# Top.net
KiCad netlist of a schematic drawn in Altium Designer
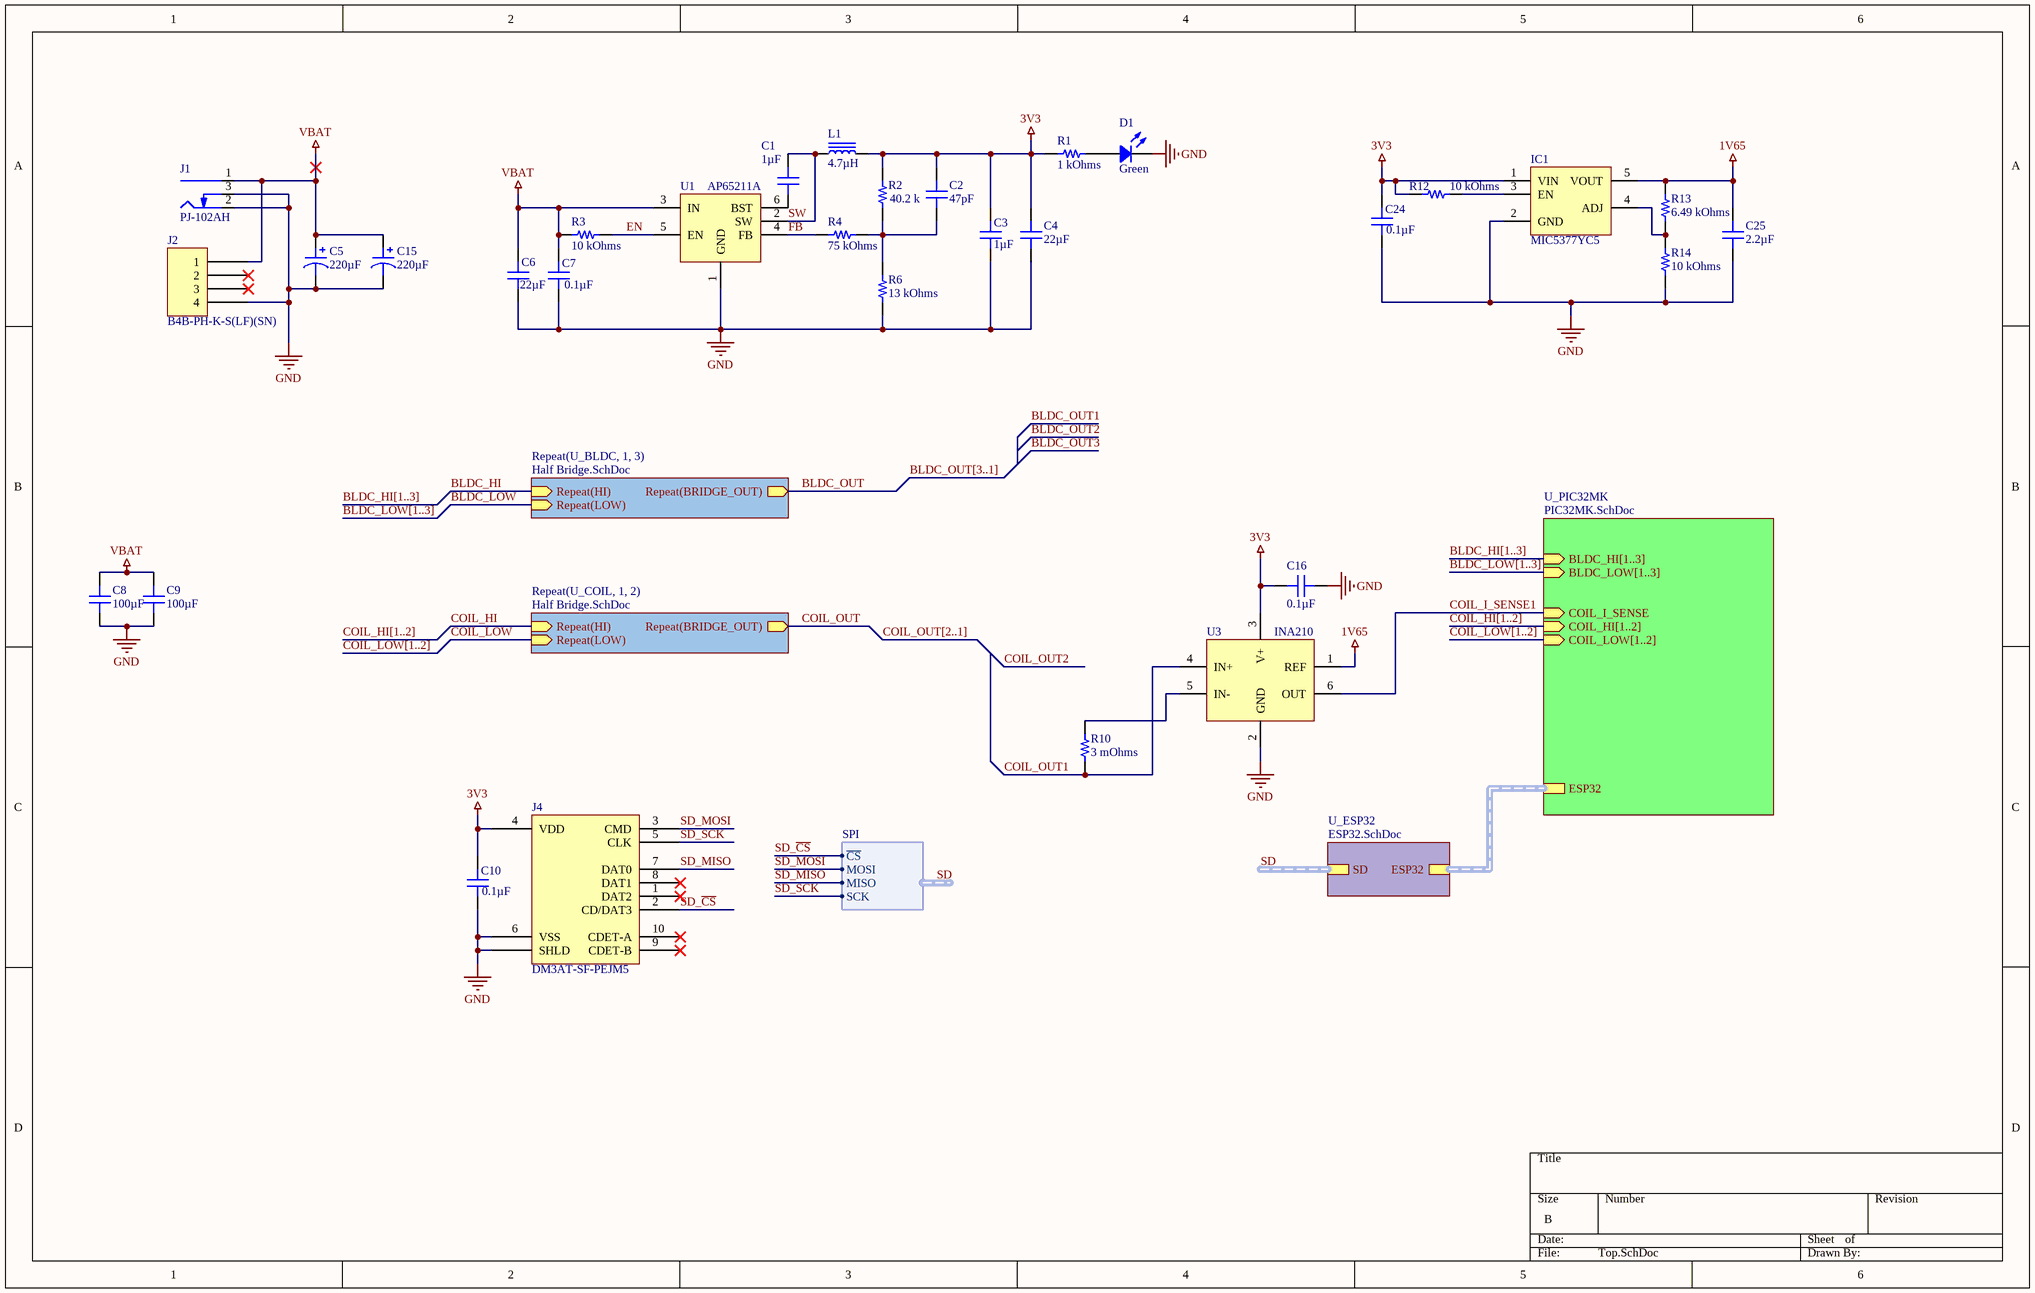
[diagram p0: Top.SchDoc]

(export (version "E")
  (design (tool "Eeschema 10.0.6"))
  (components
    (comp (ref "C1")
      (value "1µF")
      (footprint "CAP 0603_1608")
      (description "CAP CER 1UF 25V X7R 0603")
      (fields
        (field (name "PART NUMBER") "GCJ188R71E105KA01D")
        (field (name "MANUFACTURER") "Murata Electronics")
      )
      (libsource (lib "Celestial Altium Library - altium_library") (part "Capacitor"))
    )
    (comp (ref "C2")
      (value "47pF")
      (footprint "CAP 0603_1608")
      (description "CAP CER 47PF 100V NP0 0603")
      (fields
        (field (name "PART NUMBER") "C1608NP02A470J080AA")
        (field (name "MANUFACTURER") "TDK Corporation")
      )
      (libsource (lib "Celestial Altium Library - altium_library") (part "Capacitor"))
    )
    (comp (ref "C3")
      (value "1µF")
      (footprint "CAP 0603_1608")
      (description "CAP CER 1UF 25V X7R 0603")
      (fields
        (field (name "PART NUMBER") "GCJ188R71E105KA01D")
        (field (name "MANUFACTURER") "Murata Electronics")
      )
      (libsource (lib "Celestial Altium Library - altium_library") (part "Capacitor"))
    )
    (comp (ref "C4")
      (value "22µF")
      (footprint "CAP 0805_2012")
      (description "CAP CER 22UF 16V X5R 0805")
      (fields
        (field (name "PART NUMBER") "CL21A226MOQNNNE")
        (field (name "MANUFACTURER") "Samsung Electro-Mechanics")
      )
      (libsource (lib "Celestial Altium Library - altium_library") (part "Capacitor"))
    )
    (comp (ref "C5")
      (value "220µF")
      (footprint "CAP POL 2917_7343")
      (description "CAP TANT 220UF 10% 16V 2917")
      (fields (field (name "PART NUMBER") "T510X227K016ATE040") (field (name "MANUFACTURER") "KEMET"))
      (libsource (lib "Celestial Altium Library - altium_library") (part "Polarised Capacitor"))
    )
    (comp (ref "C6")
      (value "22µF")
      (footprint "CAP 0805_2012")
      (description "CAP CER 10UF 25V X7S 0805")
      (fields
        (field (name "PART NUMBER") "C2012X7S1E106K125AC")
        (field (name "MANUFACTURER") "TDK Corporation")
      )
      (libsource (lib "Celestial Altium Library - altium_library") (part "Capacitor"))
    )
    (comp (ref "C7")
      (value "0.1µF")
      (footprint "CAP 0603_1608")
      (description "CAP CER 0.1UF 100V 0603 EPOXY")
      (fields
        (field (name "PART NUMBER") "GCG188R92A104KA03D")
        (field (name "MANUFACTURER") "Murata Electronics")
      )
      (libsource (lib "Celestial Altium Library - altium_library") (part "Capacitor"))
    )
    (comp (ref "C8")
      (value "100µF")
      (footprint "CAP 1210_3225 - 2.8MM")
      (description "CAP CER 100UF 16V X5R 1210")
      (fields (field (name "PART NUMBER") "EMK325ABJ107MM-P") (field (name "MANUFACTURER") "Taiyo Yuden"))
      (libsource (lib "Celestial Altium Library - altium_library") (part "Capacitor"))
    )
    (comp (ref "C9")
      (value "100µF")
      (footprint "CAP 1210_3225 - 2.8MM")
      (description "CAP CER 100UF 16V X5R 1210")
      (fields (field (name "PART NUMBER") "EMK325ABJ107MM-P") (field (name "MANUFACTURER") "Taiyo Yuden"))
      (libsource (lib "Celestial Altium Library - altium_library") (part "Capacitor"))
    )
    (comp (ref "C10")
      (value "0.1µF")
      (footprint "CAP 0603_1608")
      (description "CAP CER 0.1UF 100V 0603 EPOXY")
      (fields
        (field (name "PART NUMBER") "GCG188R92A104KA03D")
        (field (name "MANUFACTURER") "Murata Electronics")
      )
      (libsource (lib "Celestial Altium Library - altium_library") (part "Capacitor"))
    )
    (comp (ref "C15")
      (value "220µF")
      (footprint "CAP POL 2917_7343")
      (description "CAP TANT 220UF 10% 16V 2917")
      (fields (field (name "PART NUMBER") "T510X227K016ATE040") (field (name "MANUFACTURER") "KEMET"))
      (libsource (lib "Celestial Altium Library - altium_library") (part "Polarised Capacitor"))
    )
    (comp (ref "C16")
      (value "0.1µF")
      (footprint "CAP 0603_1608")
      (description "CAP CER 0.1UF 100V 0603 EPOXY")
      (fields
        (field (name "PART NUMBER") "GCG188R92A104KA03D")
        (field (name "MANUFACTURER") "Murata Electronics")
      )
      (libsource (lib "Celestial Altium Library - altium_library") (part "Capacitor"))
    )
    (comp (ref "C24")
      (value "0.1µF")
      (footprint "CAP 0603_1608")
      (description "CAP CER 0.1UF 100V 0603 EPOXY")
      (fields
        (field (name "PART NUMBER") "GCG188R92A104KA03D")
        (field (name "MANUFACTURER") "Murata Electronics")
      )
      (libsource (lib "Celestial Altium Library - altium_library") (part "Capacitor"))
    )
    (comp (ref "C25")
      (value "2.2µF")
      (footprint "CAP 0603_1608")
      (description "CAP CER 2.2UF 6.3V Y5V 0603")
      (fields (field (name "PART NUMBER") "CC0603ZRY5V5BB225") (field (name "MANUFACTURER") "Yageo"))
      (libsource (lib "Celestial Altium Library - altium_library") (part "Capacitor"))
    )
    (comp (ref "D1")
      (value "Green")
      (footprint "LED 0603_1608 GREEN")
      (description "1.6X0.8MM LC GREEN PIXSOLED DOME")
      (fields (field (name "PART NUMBER") "XZCDGK53W-8VF") (field (name "MANUFACTURER") "SunLED"))
      (libsource (lib "Celestial Altium Library - altium_library") (part "LED"))
    )
    (comp (ref "IC1")
      (value "MIC5377YC5")
      (footprint "TI SOT-23-5 DBV")
      (description "IC REG LIN POS ADJ 150MA SOT23-5")
      (fields (field (name "MANUFACTURER") "Texas Instruments"))
      (libsource (lib "IC") (part "MIC5377YC5"))
    )
    (comp (ref "J1")
      (value "PJ-102AH")
      (footprint "CUI PJ-102AH")
      (description "CONN PWR JACK 2X5.5MM SOLDER")
      (fields (field (name "MANUFACTURER") "CUI Devices"))
      (libsource (lib "Celestial Altium Library - altium_library") (part "Barrel Connector"))
    )
    (comp (ref "J2")
      (value "B4B-PH-K-S(LF)(SN)")
      (footprint "JST B4B-PH-K")
      (description "CONN HEADER VERT 4POS 2MM")
      (fields (field (name "MANUFACTURER") "JST Sales America Inc."))
      (libsource (lib "Celestial Altium Library - altium_library") (part "4 Pin"))
    )
    (comp (ref "J4")
      (value "DM3AT-SF-PEJM5")
      (footprint "HIROSE DM3AT-SF-PEJM5")
      (description "CONN MICRO SD CARD PUSH-PUSH R/A")
      (fields (field (name "MANUFACTURER") "Hirose Electric Co Ltd"))
      (libsource (lib "Celestial Altium Library - altium_library") (part "Hirose DM3 MicroSD"))
    )
    (comp (ref "L1")
      (value "4.7µH")
      (footprint "IND 1008_2520")
      (description "FIXED IND 4.7UH 1A 110 MOHM SMD")
      (fields (field (name "PART NUMBER") "MLP2520S4R7ST0S1") (field (name "MANUFACTURER") "TDK Corporation"))
      (libsource (lib "Celestial Altium Library - altium_library") (part "Inductor"))
    )
    (comp (ref "R1")
      (value "1 kOhms")
      (footprint "RES 0603_1608")
      (description "RES 1K OHM 0.5% 1/10W 0603")
      (fields
        (field (name "PART NUMBER") "RNCF0603DTE1K00")
        (field (name "MANUFACTURER") "Stackpole Electronics Inc")
      )
      (libsource (lib "Celestial Altium Library - altium_library") (part "Resistor"))
    )
    (comp (ref "R2")
      (value "40.2 k")
      (footprint "RES 0603_1608")
      (description "RES SMD 40.2KOHM 0.5% 1/10W 0603")
      (fields (field (name "PART NUMBER") "RT0603DRD0740K2L") (field (name "MANUFACTURER") "Yageo"))
      (libsource (lib "Celestial Altium Library - altium_library") (part "Resistor"))
    )
    (comp (ref "R3")
      (value "10 kOhms")
      (footprint "RES 0603_1608")
      (description "RES 10K OHM 0.1% 1/16W 0603")
      (fields
        (field (name "PART NUMBER") "RNCS0603BKE10K0")
        (field (name "MANUFACTURER") "Stackpole Electronics Inc")
      )
      (libsource (lib "Celestial Altium Library - altium_library") (part "Resistor"))
    )
    (comp (ref "R4")
      (value "75 kOhms")
      (footprint "RES 0603_1608")
      (description "RES SMD 75K OHM 5% 1/10W 0603")
      (fields (field (name "PART NUMBER") "CR0603-JW-753ELF") (field (name "MANUFACTURER") "Bourns Inc."))
      (libsource (lib "Celestial Altium Library - altium_library") (part "Resistor"))
    )
    (comp (ref "R6")
      (value "13 kOhms")
      (footprint "RES 0603_1608")
      (description "RES SMD 13K OHM 0.1% 1/10W 0603")
      (fields (field (name "PART NUMBER") "RG1608P-133-B-T5") (field (name "MANUFACTURER") "Susumu"))
      (libsource (lib "Celestial Altium Library - altium_library") (part "Resistor"))
    )
    (comp (ref "R10")
      (value "3 mOhms")
      (footprint "STACKPOLE CSR0805")
      (description "RES 0.003 OHM 2% 1/3W 0603")
      (fields (field (name "PART NUMBER") "LVT06R0030GER") (field (name "MANUFACTURER") "Ohmite"))
      (libsource (lib "Celestial Altium Library - altium_library") (part "Resistor"))
    )
    (comp (ref "R12")
      (value "10 kOhms")
      (footprint "RES 0603_1608")
      (description "RES 10K OHM 0.1% 1/16W 0603")
      (fields
        (field (name "PART NUMBER") "RNCS0603BKE10K0")
        (field (name "MANUFACTURER") "Stackpole Electronics Inc")
      )
      (libsource (lib "Celestial Altium Library - altium_library") (part "Resistor"))
    )
    (comp (ref "R13")
      (value "6.49 kOhms")
      (footprint "RES 0603_1608")
      (description "RES SMD 6.49K OHM 1% 1/10W 0603")
      (fields (field (name "PART NUMBER") "RC0603FR-076K49L") (field (name "MANUFACTURER") "Yageo"))
      (libsource (lib "Celestial Altium Library - altium_library") (part "Resistor"))
    )
    (comp (ref "R14")
      (value "10 kOhms")
      (footprint "RES 0603_1608")
      (description "RES 10K OHM 0.1% 1/16W 0603")
      (fields
        (field (name "PART NUMBER") "RNCS0603BKE10K0")
        (field (name "MANUFACTURER") "Stackpole Electronics Inc")
      )
      (libsource (lib "Celestial Altium Library - altium_library") (part "Resistor"))
    )
    (comp (ref "U1")
      (value "AP65211A")
      (footprint "TSOT-26-6")
      (description "ADJ step down Buck")
      (libsource (lib "IC") (part "AP65211A"))
    )
    (comp (ref "U3")
      (value "INA210")
      (footprint "TI SC70-6 DCK")
      (description "Current sense amplifier")
      (libsource (lib "IC") (part "INA210"))
    )
  )
  (nets
    (net (code "24") (name "/COIL_I_SENSE1") (class "Default")
      (node (ref "U3") (pin "6") (pinfunction "OUT_6") (pintype "passive"))
    )
    (net (code "28") (name "/COIL_OUT1") (class "Default")
      (node (ref "R10") (pin "1") (pinfunction "1_1") (pintype "passive"))
      (node (ref "U3") (pin "4") (pinfunction "IN+_4") (pintype "passive"))
    )
    (net (code "31") (name "/EN") (class "Default")
      (node (ref "R3") (pin "1") (pinfunction "1_1") (pintype "passive"))
      (node (ref "U1") (pin "5") (pinfunction "EN_5") (pintype "passive"))
    )
    (net (code "33") (name "/FB") (class "Default")
      (node (ref "R4") (pin "1") (pinfunction "1_1") (pintype "passive"))
      (node (ref "U1") (pin "4") (pinfunction "FB_4") (pintype "passive"))
    )
    (net (code "34") (name "/SD_MISO") (class "Default")
      (node (ref "J4") (pin "7") (pinfunction "DAT0_7") (pintype "passive"))
    )
    (net (code "35") (name "/SD_MOSI") (class "Default")
      (node (ref "J4") (pin "3") (pinfunction "CMD_3") (pintype "passive"))
    )
    (net (code "36") (name "/SD_SCK") (class "Default")
      (node (ref "J4") (pin "5") (pinfunction "CLK_5") (pintype "passive"))
    )
    (net (code "37") (name "/SD_~{CS}") (class "Default")
      (node (ref "J4") (pin "2") (pinfunction "CD/DAT3_2") (pintype "passive"))
    )
    (net (code "39") (name "/SW") (class "Default")
      (node (ref "C1") (pin "1") (pinfunction "1_1") (pintype "passive"))
      (node (ref "L1") (pin "1") (pinfunction "1_1") (pintype "passive"))
      (node (ref "U1") (pin "2") (pinfunction "SW_2") (pintype "passive"))
    )
    (net (code "41") (name "1V65") (class "Default")
      (node (ref "C25") (pin "2") (pinfunction "2_2") (pintype "passive"))
      (node (ref "IC1") (pin "5") (pinfunction "VOUT_5") (pintype "passive"))
      (node (ref "R13") (pin "2") (pinfunction "2_2") (pintype "passive"))
      (node (ref "U3") (pin "1") (pinfunction "REF_1") (pintype "passive"))
    )
    (net (code "42") (name "3V3") (class "Default")
      (node (ref "C10") (pin "1") (pinfunction "1_1") (pintype "passive"))
      (node (ref "C16") (pin "1") (pinfunction "1_1") (pintype "passive"))
      (node (ref "C2") (pin "2") (pinfunction "2_2") (pintype "passive"))
      (node (ref "C24") (pin "1") (pinfunction "1_1") (pintype "passive"))
      (node (ref "C3") (pin "2") (pinfunction "2_2") (pintype "passive"))
      (node (ref "C4") (pin "2") (pinfunction "2_2") (pintype "passive"))
      (node (ref "IC1") (pin "1") (pinfunction "VIN_1") (pintype "passive"))
      (node (ref "J4") (pin "4") (pinfunction "VDD_4") (pintype "passive"))
      (node (ref "L1") (pin "2") (pinfunction "2_2") (pintype "passive"))
      (node (ref "R1") (pin "1") (pinfunction "1_1") (pintype "passive"))
      (node (ref "R12") (pin "2") (pinfunction "2_2") (pintype "passive"))
      (node (ref "R2") (pin "2") (pinfunction "2_2") (pintype "passive"))
      (node (ref "U3") (pin "3") (pinfunction "V+_3") (pintype "passive"))
    )
    (net (code "43") (name "GND") (class "Default")
      (node (ref "C10") (pin "2") (pinfunction "2_2") (pintype "passive"))
      (node (ref "C15") (pin "2") (pinfunction "2_2") (pintype "passive"))
      (node (ref "C16") (pin "2") (pinfunction "2_2") (pintype "passive"))
      (node (ref "C24") (pin "2") (pinfunction "2_2") (pintype "passive"))
      (node (ref "C25") (pin "1") (pinfunction "1_1") (pintype "passive"))
      (node (ref "C3") (pin "1") (pinfunction "1_1") (pintype "passive"))
      (node (ref "C4") (pin "1") (pinfunction "1_1") (pintype "passive"))
      (node (ref "C5") (pin "2") (pinfunction "2_2") (pintype "passive"))
      (node (ref "C6") (pin "1") (pinfunction "1_1") (pintype "passive"))
      (node (ref "C7") (pin "2") (pinfunction "2_2") (pintype "passive"))
      (node (ref "C8") (pin "1") (pinfunction "1_1") (pintype "passive"))
      (node (ref "C9") (pin "1") (pinfunction "1_1") (pintype "passive"))
      (node (ref "D1") (pin "2") (pinfunction "2_2") (pintype "passive"))
      (node (ref "IC1") (pin "2") (pinfunction "GND_2") (pintype "passive"))
      (node (ref "J1") (pin "2") (pinfunction "Outer_2") (pintype "passive"))
      (node (ref "J1") (pin "3") (pinfunction "SW_3") (pintype "passive"))
      (node (ref "J2") (pin "4") (pinfunction "4_4") (pintype "passive"))
      (node (ref "J4") (pin "6") (pinfunction "VSS_6") (pintype "passive"))
      (node (ref "J4") (pin "S") (pinfunction "SHLD_S") (pintype "passive"))
      (node (ref "R14") (pin "1") (pinfunction "1_1") (pintype "passive"))
      (node (ref "R6") (pin "1") (pinfunction "1_1") (pintype "passive"))
      (node (ref "U1") (pin "1") (pinfunction "GND_1") (pintype "passive"))
      (node (ref "U3") (pin "2") (pinfunction "GND_2") (pintype "passive"))
    )
    (net (code "44") (name "Net-(C2-Pad1)") (class "Default")
      (node (ref "C2") (pin "1") (pinfunction "1_1") (pintype "passive"))
      (node (ref "R2") (pin "1") (pinfunction "1_1") (pintype "passive"))
      (node (ref "R4") (pin "2") (pinfunction "2_2") (pintype "passive"))
      (node (ref "R6") (pin "2") (pinfunction "2_2") (pintype "passive"))
    )
    (net (code "45") (name "Net-(D1-Pad1)") (class "Default")
      (node (ref "D1") (pin "1") (pinfunction "1_1") (pintype "passive"))
      (node (ref "R1") (pin "2") (pinfunction "2_2") (pintype "passive"))
    )
    (net (code "46") (name "Net-(IC1-ADJ)") (class "Default")
      (node (ref "IC1") (pin "4") (pinfunction "ADJ_4") (pintype "passive"))
      (node (ref "R13") (pin "1") (pinfunction "1_1") (pintype "passive"))
      (node (ref "R14") (pin "2") (pinfunction "2_2") (pintype "passive"))
    )
    (net (code "47") (name "Net-(IC1-EN)") (class "Default")
      (node (ref "IC1") (pin "3") (pinfunction "EN_3") (pintype "passive"))
      (node (ref "R12") (pin "1") (pinfunction "1_1") (pintype "passive"))
    )
    (net (code "48") (name "Net-(U1-BST)") (class "Default")
      (node (ref "C1") (pin "2") (pinfunction "2_2") (pintype "passive"))
      (node (ref "U1") (pin "6") (pinfunction "BST_6") (pintype "passive"))
    )
    (net (code "49") (name "Net-(U3-IN-)") (class "Default")
      (node (ref "R10") (pin "2") (pinfunction "2_2") (pintype "passive"))
      (node (ref "U3") (pin "5") (pinfunction "IN-_5") (pintype "passive"))
    )
    (net (code "50") (name "VBAT") (class "Default")
      (node (ref "C15") (pin "1") (pinfunction "1_1") (pintype "passive"))
      (node (ref "C5") (pin "1") (pinfunction "1_1") (pintype "passive"))
      (node (ref "C6") (pin "2") (pinfunction "2_2") (pintype "passive"))
      (node (ref "C7") (pin "1") (pinfunction "1_1") (pintype "passive"))
      (node (ref "C8") (pin "2") (pinfunction "2_2") (pintype "passive"))
      (node (ref "C9") (pin "2") (pinfunction "2_2") (pintype "passive"))
      (node (ref "J1") (pin "1") (pinfunction "Centre_1") (pintype "passive"))
      (node (ref "J2") (pin "1") (pinfunction "1_1") (pintype "passive"))
      (node (ref "R3") (pin "2") (pinfunction "2_2") (pintype "passive"))
      (node (ref "U1") (pin "3") (pinfunction "IN_3") (pintype "passive"))
    )
    (net (code "51") (name "unconnected-(J2-Pad2)") (class "Default")
      (node (ref "J2") (pin "2") (pinfunction "2_2") (pintype "passive+no_connect"))
    )
    (net (code "52") (name "unconnected-(J2-Pad3)") (class "Default")
      (node (ref "J2") (pin "3") (pinfunction "3_3") (pintype "passive+no_connect"))
    )
    (net (code "53") (name "unconnected-(J4-CDET-A-Pad10)") (class "Default")
      (node (ref "J4") (pin "10") (pinfunction "CDET-A_10") (pintype "passive+no_connect"))
    )
    (net (code "54") (name "unconnected-(J4-CDET-B-Pad9)") (class "Default")
      (node (ref "J4") (pin "9") (pinfunction "CDET-B_9") (pintype "passive+no_connect"))
    )
    (net (code "55") (name "unconnected-(J4-DAT1-Pad8)") (class "Default")
      (node (ref "J4") (pin "8") (pinfunction "DAT1_8") (pintype "passive+no_connect"))
    )
    (net (code "56") (name "unconnected-(J4-DAT2-Pad1)") (class "Default")
      (node (ref "J4") (pin "1") (pinfunction "DAT2_1") (pintype "passive+no_connect"))
    )
  )
)
